# id_eeprom.net
KiCad netlist of a schematic drawn in EAGLE
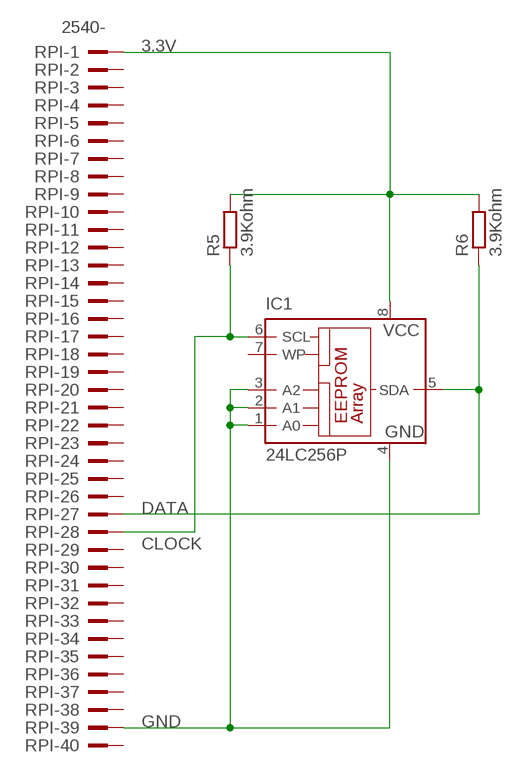
[diagram p0: schematic, sheet 1]

(export (version "E")
  (design (tool "Eeschema 10.0.6"))
  (components
    (comp (ref "IC1")
      (value "24LC256P")
      (footprint "eagle-import:DIL8")
      (libsource (lib "eagle-import") (part "24PLC256"))
    )
    (comp (ref "R5")
      (value "3.9Kohm")
      (footprint "eagle-import:0207_7")
      (libsource (lib "eagle-import") (part "R-EU_0207/7"))
    )
    (comp (ref "R6")
      (value "3.9Kohm")
      (footprint "eagle-import:0207_7")
      (libsource (lib "eagle-import") (part "R-EU_0207/7"))
    )
    (comp (ref "RPI")
      (value "2540-")
      (footprint "eagle-import:PAK100_2500-40")
      (libsource (lib "eagle-import") (part "2540-"))
    )
  )
  (nets
    (net (code "1") (name "/3.3V") (class "Default")
      (node (ref "IC1") (pin "8") (pinfunction "VCC_8") (pintype "power_in"))
      (node (ref "R5") (pin "2") (pinfunction "2_2") (pintype "passive"))
      (node (ref "R6") (pin "2") (pinfunction "2_2") (pintype "passive"))
      (node (ref "RPI") (pin "1") (pinfunction "KL_1") (pintype "passive"))
    )
    (net (code "2") (name "/CLOCK") (class "Default")
      (node (ref "IC1") (pin "6") (pinfunction "SCL_6") (pintype "input"))
      (node (ref "R5") (pin "1") (pinfunction "1_1") (pintype "passive"))
      (node (ref "RPI") (pin "28") (pinfunction "KL_28") (pintype "passive"))
    )
    (net (code "3") (name "/DATA") (class "Default")
      (node (ref "IC1") (pin "5") (pinfunction "SDA_5") (pintype "bidirectional"))
      (node (ref "R6") (pin "1") (pinfunction "1_1") (pintype "passive"))
      (node (ref "RPI") (pin "27") (pinfunction "KL_27") (pintype "passive"))
    )
    (net (code "4") (name "/GND") (class "Default")
      (node (ref "IC1") (pin "1") (pinfunction "A0_1") (pintype "input"))
      (node (ref "IC1") (pin "2") (pinfunction "A1_2") (pintype "input"))
      (node (ref "IC1") (pin "3") (pinfunction "A2_3") (pintype "input"))
      (node (ref "IC1") (pin "4") (pinfunction "GND_4") (pintype "power_in"))
      (node (ref "RPI") (pin "39") (pinfunction "KL_39") (pintype "passive"))
    )
    (net (code "5") (name "unconnected-(IC1-WP-Pad7)") (class "Default")
      (node (ref "IC1") (pin "7") (pinfunction "WP_7") (pintype "input"))
    )
    (net (code "6") (name "unconnected-(RPIAA-KL-Pad33)") (class "Default")
      (node (ref "RPI") (pin "33") (pinfunction "KL_33") (pintype "passive"))
    )
    (net (code "7") (name "unconnected-(RPIAB-KL-Pad34)") (class "Default")
      (node (ref "RPI") (pin "34") (pinfunction "KL_34") (pintype "passive"))
    )
    (net (code "8") (name "unconnected-(RPIAC-KL-Pad35)") (class "Default")
      (node (ref "RPI") (pin "35") (pinfunction "KL_35") (pintype "passive"))
    )
    (net (code "9") (name "unconnected-(RPIAD-KL-Pad36)") (class "Default")
      (node (ref "RPI") (pin "36") (pinfunction "KL_36") (pintype "passive"))
    )
    (net (code "10") (name "unconnected-(RPIAE-KL-Pad37)") (class "Default")
      (node (ref "RPI") (pin "37") (pinfunction "KL_37") (pintype "passive"))
    )
    (net (code "11") (name "unconnected-(RPIAF-KL-Pad38)") (class "Default")
      (node (ref "RPI") (pin "38") (pinfunction "KL_38") (pintype "passive"))
    )
    (net (code "12") (name "unconnected-(RPIAH-KL-Pad4)") (class "Default")
      (node (ref "RPI") (pin "4") (pinfunction "KL_4") (pintype "passive"))
    )
    (net (code "13") (name "unconnected-(RPIAI-KL-Pad40)") (class "Default")
      (node (ref "RPI") (pin "40") (pinfunction "KL_40") (pintype "passive"))
    )
    (net (code "14") (name "unconnected-(RPIAJ-KL-Pad5)") (class "Default")
      (node (ref "RPI") (pin "5") (pinfunction "KL_5") (pintype "passive"))
    )
    (net (code "15") (name "unconnected-(RPIAK-KL-Pad6)") (class "Default")
      (node (ref "RPI") (pin "6") (pinfunction "KL_6") (pintype "passive"))
    )
    (net (code "16") (name "unconnected-(RPIAL-KL-Pad7)") (class "Default")
      (node (ref "RPI") (pin "7") (pinfunction "KL_7") (pintype "passive"))
    )
    (net (code "17") (name "unconnected-(RPIAM-KL-Pad8)") (class "Default")
      (node (ref "RPI") (pin "8") (pinfunction "KL_8") (pintype "passive"))
    )
    (net (code "18") (name "unconnected-(RPIAN-KL-Pad9)") (class "Default")
      (node (ref "RPI") (pin "9") (pinfunction "KL_9") (pintype "passive"))
    )
    (net (code "19") (name "unconnected-(RPIB-KL-Pad10)") (class "Default")
      (node (ref "RPI") (pin "10") (pinfunction "KL_10") (pintype "passive"))
    )
    (net (code "20") (name "unconnected-(RPIC-KL-Pad11)") (class "Default")
      (node (ref "RPI") (pin "11") (pinfunction "KL_11") (pintype "passive"))
    )
    (net (code "21") (name "unconnected-(RPID-KL-Pad12)") (class "Default")
      (node (ref "RPI") (pin "12") (pinfunction "KL_12") (pintype "passive"))
    )
    (net (code "22") (name "unconnected-(RPIE-KL-Pad13)") (class "Default")
      (node (ref "RPI") (pin "13") (pinfunction "KL_13") (pintype "passive"))
    )
    (net (code "23") (name "unconnected-(RPIF-KL-Pad14)") (class "Default")
      (node (ref "RPI") (pin "14") (pinfunction "KL_14") (pintype "passive"))
    )
    (net (code "24") (name "unconnected-(RPIG-KL-Pad15)") (class "Default")
      (node (ref "RPI") (pin "15") (pinfunction "KL_15") (pintype "passive"))
    )
    (net (code "25") (name "unconnected-(RPIH-KL-Pad16)") (class "Default")
      (node (ref "RPI") (pin "16") (pinfunction "KL_16") (pintype "passive"))
    )
    (net (code "26") (name "unconnected-(RPII-KL-Pad17)") (class "Default")
      (node (ref "RPI") (pin "17") (pinfunction "KL_17") (pintype "passive"))
    )
    (net (code "27") (name "unconnected-(RPIJ-KL-Pad18)") (class "Default")
      (node (ref "RPI") (pin "18") (pinfunction "KL_18") (pintype "passive"))
    )
    (net (code "28") (name "unconnected-(RPIK-KL-Pad19)") (class "Default")
      (node (ref "RPI") (pin "19") (pinfunction "KL_19") (pintype "passive"))
    )
    (net (code "29") (name "unconnected-(RPIL-KL-Pad2)") (class "Default")
      (node (ref "RPI") (pin "2") (pinfunction "KL_2") (pintype "passive"))
    )
    (net (code "30") (name "unconnected-(RPIM-KL-Pad20)") (class "Default")
      (node (ref "RPI") (pin "20") (pinfunction "KL_20") (pintype "passive"))
    )
    (net (code "31") (name "unconnected-(RPIN-KL-Pad21)") (class "Default")
      (node (ref "RPI") (pin "21") (pinfunction "KL_21") (pintype "passive"))
    )
    (net (code "32") (name "unconnected-(RPIO-KL-Pad22)") (class "Default")
      (node (ref "RPI") (pin "22") (pinfunction "KL_22") (pintype "passive"))
    )
    (net (code "33") (name "unconnected-(RPIP-KL-Pad23)") (class "Default")
      (node (ref "RPI") (pin "23") (pinfunction "KL_23") (pintype "passive"))
    )
    (net (code "34") (name "unconnected-(RPIQ-KL-Pad24)") (class "Default")
      (node (ref "RPI") (pin "24") (pinfunction "KL_24") (pintype "passive"))
    )
    (net (code "35") (name "unconnected-(RPIR-KL-Pad25)") (class "Default")
      (node (ref "RPI") (pin "25") (pinfunction "KL_25") (pintype "passive"))
    )
    (net (code "36") (name "unconnected-(RPIS-KL-Pad26)") (class "Default")
      (node (ref "RPI") (pin "26") (pinfunction "KL_26") (pintype "passive"))
    )
    (net (code "37") (name "unconnected-(RPIV-KL-Pad29)") (class "Default")
      (node (ref "RPI") (pin "29") (pinfunction "KL_29") (pintype "passive"))
    )
    (net (code "38") (name "unconnected-(RPIW-KL-Pad3)") (class "Default")
      (node (ref "RPI") (pin "3") (pinfunction "KL_3") (pintype "passive"))
    )
    (net (code "39") (name "unconnected-(RPIX-KL-Pad30)") (class "Default")
      (node (ref "RPI") (pin "30") (pinfunction "KL_30") (pintype "passive"))
    )
    (net (code "40") (name "unconnected-(RPIY-KL-Pad31)") (class "Default")
      (node (ref "RPI") (pin "31") (pinfunction "KL_31") (pintype "passive"))
    )
    (net (code "41") (name "unconnected-(RPIZ-KL-Pad32)") (class "Default")
      (node (ref "RPI") (pin "32") (pinfunction "KL_32") (pintype "passive"))
    )
  )
)
